# Sheet1.net
KiCad netlist of a schematic drawn in Altium Designer
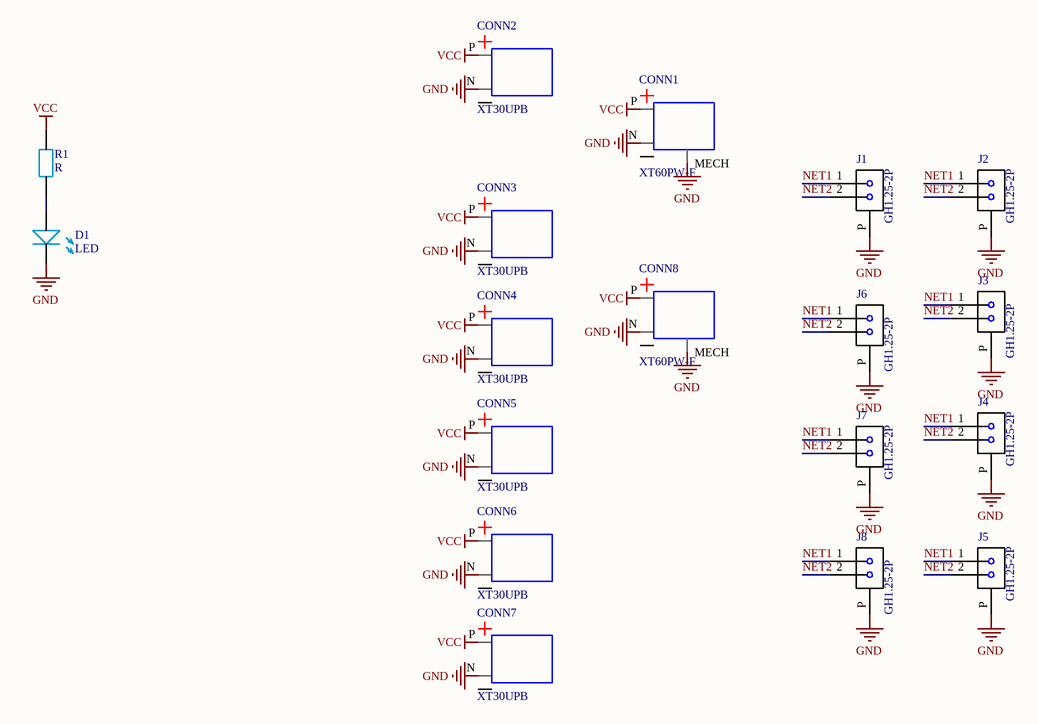
[diagram p0: Sheet1.SchDoc]

(export (version "E")
  (design (tool "Eeschema 10.0.6"))
  (components
    (comp (ref "CONN1")
      (value "XT60PW-F")
      (footprint "XT60PW-F")
      (description "卧式焊板XT60（母）")
      (libsource (lib "RM私人定制") (part "XT60PW-F"))
    )
    (comp (ref "CONN2")
      (value "XT30UPB")
      (footprint "XT30UPB")
      (description "立式焊板XT30（通用）")
      (libsource (lib "RM私人定制") (part "XT30UPB"))
    )
    (comp (ref "CONN3")
      (value "XT30UPB")
      (footprint "XT30UPB")
      (description "立式焊板XT30（通用）")
      (libsource (lib "RM私人定制") (part "XT30UPB"))
    )
    (comp (ref "CONN4")
      (value "XT30UPB")
      (footprint "XT30UPB")
      (description "立式焊板XT30（通用）")
      (libsource (lib "RM私人定制") (part "XT30UPB"))
    )
    (comp (ref "CONN5")
      (value "XT30UPB")
      (footprint "XT30UPB")
      (description "立式焊板XT30（通用）")
      (libsource (lib "RM私人定制") (part "XT30UPB"))
    )
    (comp (ref "CONN6")
      (value "XT30UPB")
      (footprint "XT30UPB")
      (description "立式焊板XT30（通用）")
      (libsource (lib "RM私人定制") (part "XT30UPB"))
    )
    (comp (ref "CONN7")
      (value "XT30UPB")
      (footprint "XT30UPB")
      (description "立式焊板XT30（通用）")
      (libsource (lib "RM私人定制") (part "XT30UPB"))
    )
    (comp (ref "CONN8")
      (value "XT60PW-F")
      (footprint "XT60PW-F")
      (description "卧式焊板XT60（母）")
      (libsource (lib "RM私人定制") (part "XT60PW-F"))
    )
    (comp (ref "D1") (value "LED") (footprint "0805二极管") (libsource (lib "elin私人订制") (part "LED")))
    (comp (ref "J1")
      (value "GH1.25-2P")
      (footprint "gh1.25-2p-立")
      (fields (field (name "MP") "53261-0271") (field (name "MF") "Molex"))
      (libsource (lib "RM私人定制") (part "GH1.25-2P"))
    )
    (comp (ref "J2")
      (value "GH1.25-2P")
      (footprint "gh1.25-2p-立")
      (fields (field (name "MP") "53261-0271") (field (name "MF") "Molex"))
      (libsource (lib "RM私人定制") (part "GH1.25-2P"))
    )
    (comp (ref "J3")
      (value "GH1.25-2P")
      (footprint "gh1.25-2p-立")
      (fields (field (name "MP") "53261-0271") (field (name "MF") "Molex"))
      (libsource (lib "RM私人定制") (part "GH1.25-2P"))
    )
    (comp (ref "J4")
      (value "GH1.25-2P")
      (footprint "gh1.25-2p-立")
      (fields (field (name "MP") "53261-0271") (field (name "MF") "Molex"))
      (libsource (lib "RM私人定制") (part "GH1.25-2P"))
    )
    (comp (ref "J5")
      (value "GH1.25-2P")
      (footprint "gh1.25-2p-立")
      (fields (field (name "MP") "53261-0271") (field (name "MF") "Molex"))
      (libsource (lib "RM私人定制") (part "GH1.25-2P"))
    )
    (comp (ref "J6")
      (value "GH1.25-2P")
      (footprint "gh1.25-2p-立")
      (fields (field (name "MP") "53261-0271") (field (name "MF") "Molex"))
      (libsource (lib "RM私人定制") (part "GH1.25-2P"))
    )
    (comp (ref "J7")
      (value "GH1.25-2P")
      (footprint "gh1.25-2p-立")
      (fields (field (name "MP") "53261-0271") (field (name "MF") "Molex"))
      (libsource (lib "RM私人定制") (part "GH1.25-2P"))
    )
    (comp (ref "J8")
      (value "GH1.25-2P")
      (footprint "gh1.25-2p-立")
      (fields (field (name "MP") "53261-0271") (field (name "MF") "Molex"))
      (libsource (lib "RM私人定制") (part "GH1.25-2P"))
    )
    (comp (ref "R1") (value "R") (footprint "0805_R") (libsource (lib "elin私人订制") (part "R")))
  )
  (nets
    (net (code "1") (name "/NET1") (class "Default")
      (node (ref "J1") (pin "1") (pinfunction "1_1") (pintype "passive"))
      (node (ref "J2") (pin "1") (pinfunction "1_1") (pintype "passive"))
      (node (ref "J3") (pin "1") (pinfunction "1_1") (pintype "passive"))
      (node (ref "J4") (pin "1") (pinfunction "1_1") (pintype "passive"))
      (node (ref "J5") (pin "1") (pinfunction "1_1") (pintype "passive"))
      (node (ref "J6") (pin "1") (pinfunction "1_1") (pintype "passive"))
      (node (ref "J7") (pin "1") (pinfunction "1_1") (pintype "passive"))
      (node (ref "J8") (pin "1") (pinfunction "1_1") (pintype "passive"))
    )
    (net (code "2") (name "/NET2") (class "Default")
      (node (ref "J1") (pin "2") (pinfunction "2_2") (pintype "passive"))
      (node (ref "J2") (pin "2") (pinfunction "2_2") (pintype "passive"))
      (node (ref "J3") (pin "2") (pinfunction "2_2") (pintype "passive"))
      (node (ref "J4") (pin "2") (pinfunction "2_2") (pintype "passive"))
      (node (ref "J5") (pin "2") (pinfunction "2_2") (pintype "passive"))
      (node (ref "J6") (pin "2") (pinfunction "2_2") (pintype "passive"))
      (node (ref "J7") (pin "2") (pinfunction "2_2") (pintype "passive"))
      (node (ref "J8") (pin "2") (pinfunction "2_2") (pintype "passive"))
    )
    (net (code "3") (name "GND") (class "Default")
      (node (ref "CONN1") (pin "3") (pinfunction "MECH_3") (pintype "passive"))
      (node (ref "CONN1") (pin "N") (pintype "passive"))
      (node (ref "CONN2") (pin "N") (pintype "passive"))
      (node (ref "CONN3") (pin "N") (pintype "passive"))
      (node (ref "CONN4") (pin "N") (pintype "passive"))
      (node (ref "CONN5") (pin "N") (pintype "passive"))
      (node (ref "CONN6") (pin "N") (pintype "passive"))
      (node (ref "CONN7") (pin "N") (pintype "passive"))
      (node (ref "CONN8") (pin "3") (pinfunction "MECH_3") (pintype "passive"))
      (node (ref "CONN8") (pin "N") (pintype "passive"))
      (node (ref "D1") (pin "2") (pinfunction "2_2") (pintype "passive"))
      (node (ref "J1") (pin "P") (pinfunction "3_P") (pintype "passive"))
      (node (ref "J2") (pin "P") (pinfunction "3_P") (pintype "passive"))
      (node (ref "J3") (pin "P") (pinfunction "3_P") (pintype "passive"))
      (node (ref "J4") (pin "P") (pinfunction "3_P") (pintype "passive"))
      (node (ref "J5") (pin "P") (pinfunction "3_P") (pintype "passive"))
      (node (ref "J6") (pin "P") (pinfunction "3_P") (pintype "passive"))
      (node (ref "J7") (pin "P") (pinfunction "3_P") (pintype "passive"))
      (node (ref "J8") (pin "P") (pinfunction "3_P") (pintype "passive"))
    )
    (net (code "4") (name "Net-(D1-Pad1)") (class "Default")
      (node (ref "D1") (pin "1") (pinfunction "1_1") (pintype "passive"))
      (node (ref "R1") (pin "1") (pinfunction "1_1") (pintype "passive"))
    )
    (net (code "5") (name "VCC") (class "Default")
      (node (ref "CONN1") (pin "P") (pintype "passive"))
      (node (ref "CONN2") (pin "P") (pintype "passive"))
      (node (ref "CONN3") (pin "P") (pintype "passive"))
      (node (ref "CONN4") (pin "P") (pintype "passive"))
      (node (ref "CONN5") (pin "P") (pintype "passive"))
      (node (ref "CONN6") (pin "P") (pintype "passive"))
      (node (ref "CONN7") (pin "P") (pintype "passive"))
      (node (ref "CONN8") (pin "P") (pintype "passive"))
      (node (ref "R1") (pin "2") (pinfunction "2_2") (pintype "passive"))
    )
  )
)
